# P15_4G_5G_NVME.net
KiCad netlist of a schematic drawn in Altium Designer
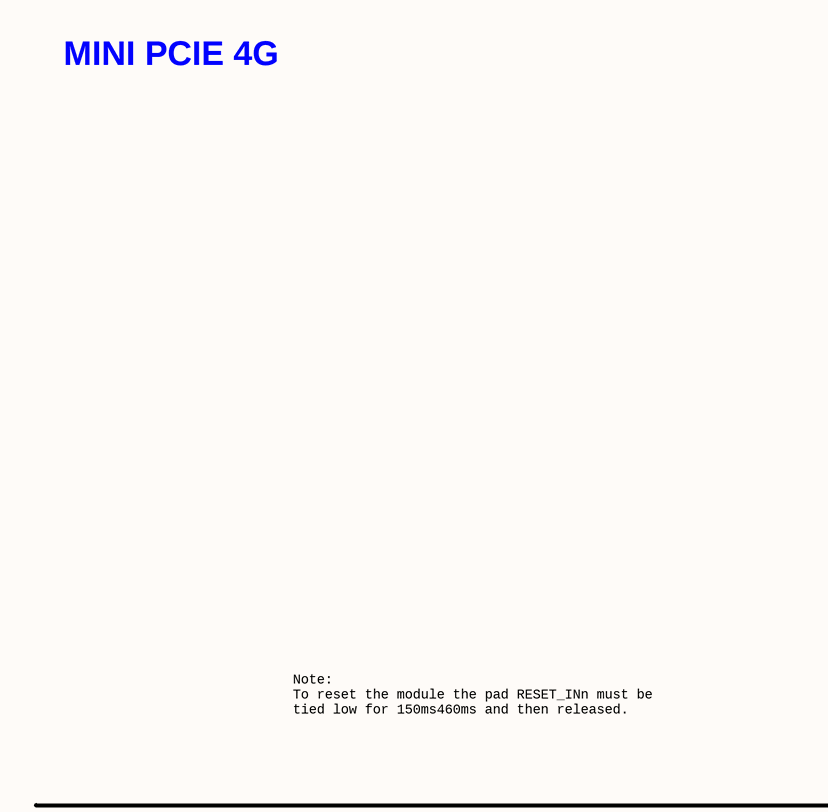
[diagram p0: P15_4G_5G_NVME.SchDoc, top left]
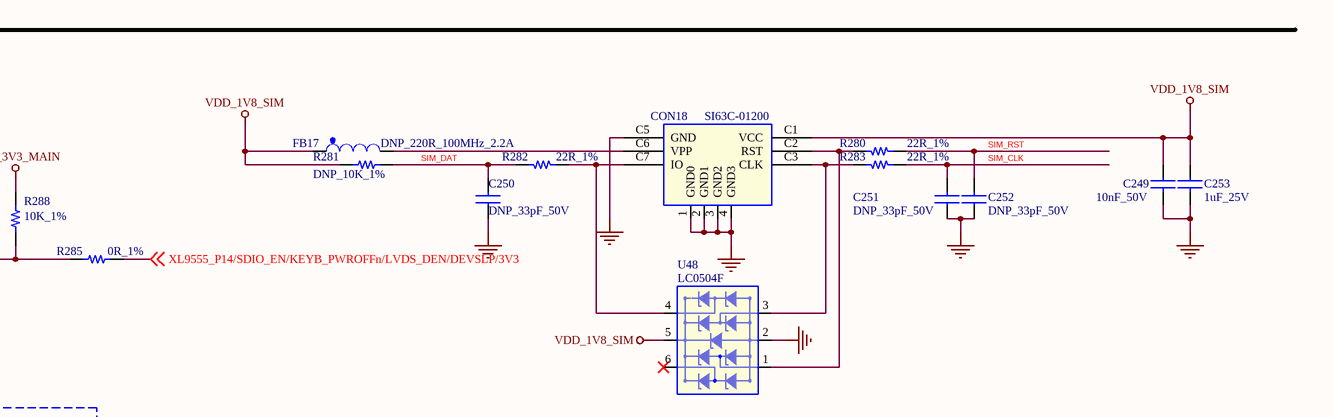
[diagram p1: P15_4G_5G_NVME.SchDoc, top right]
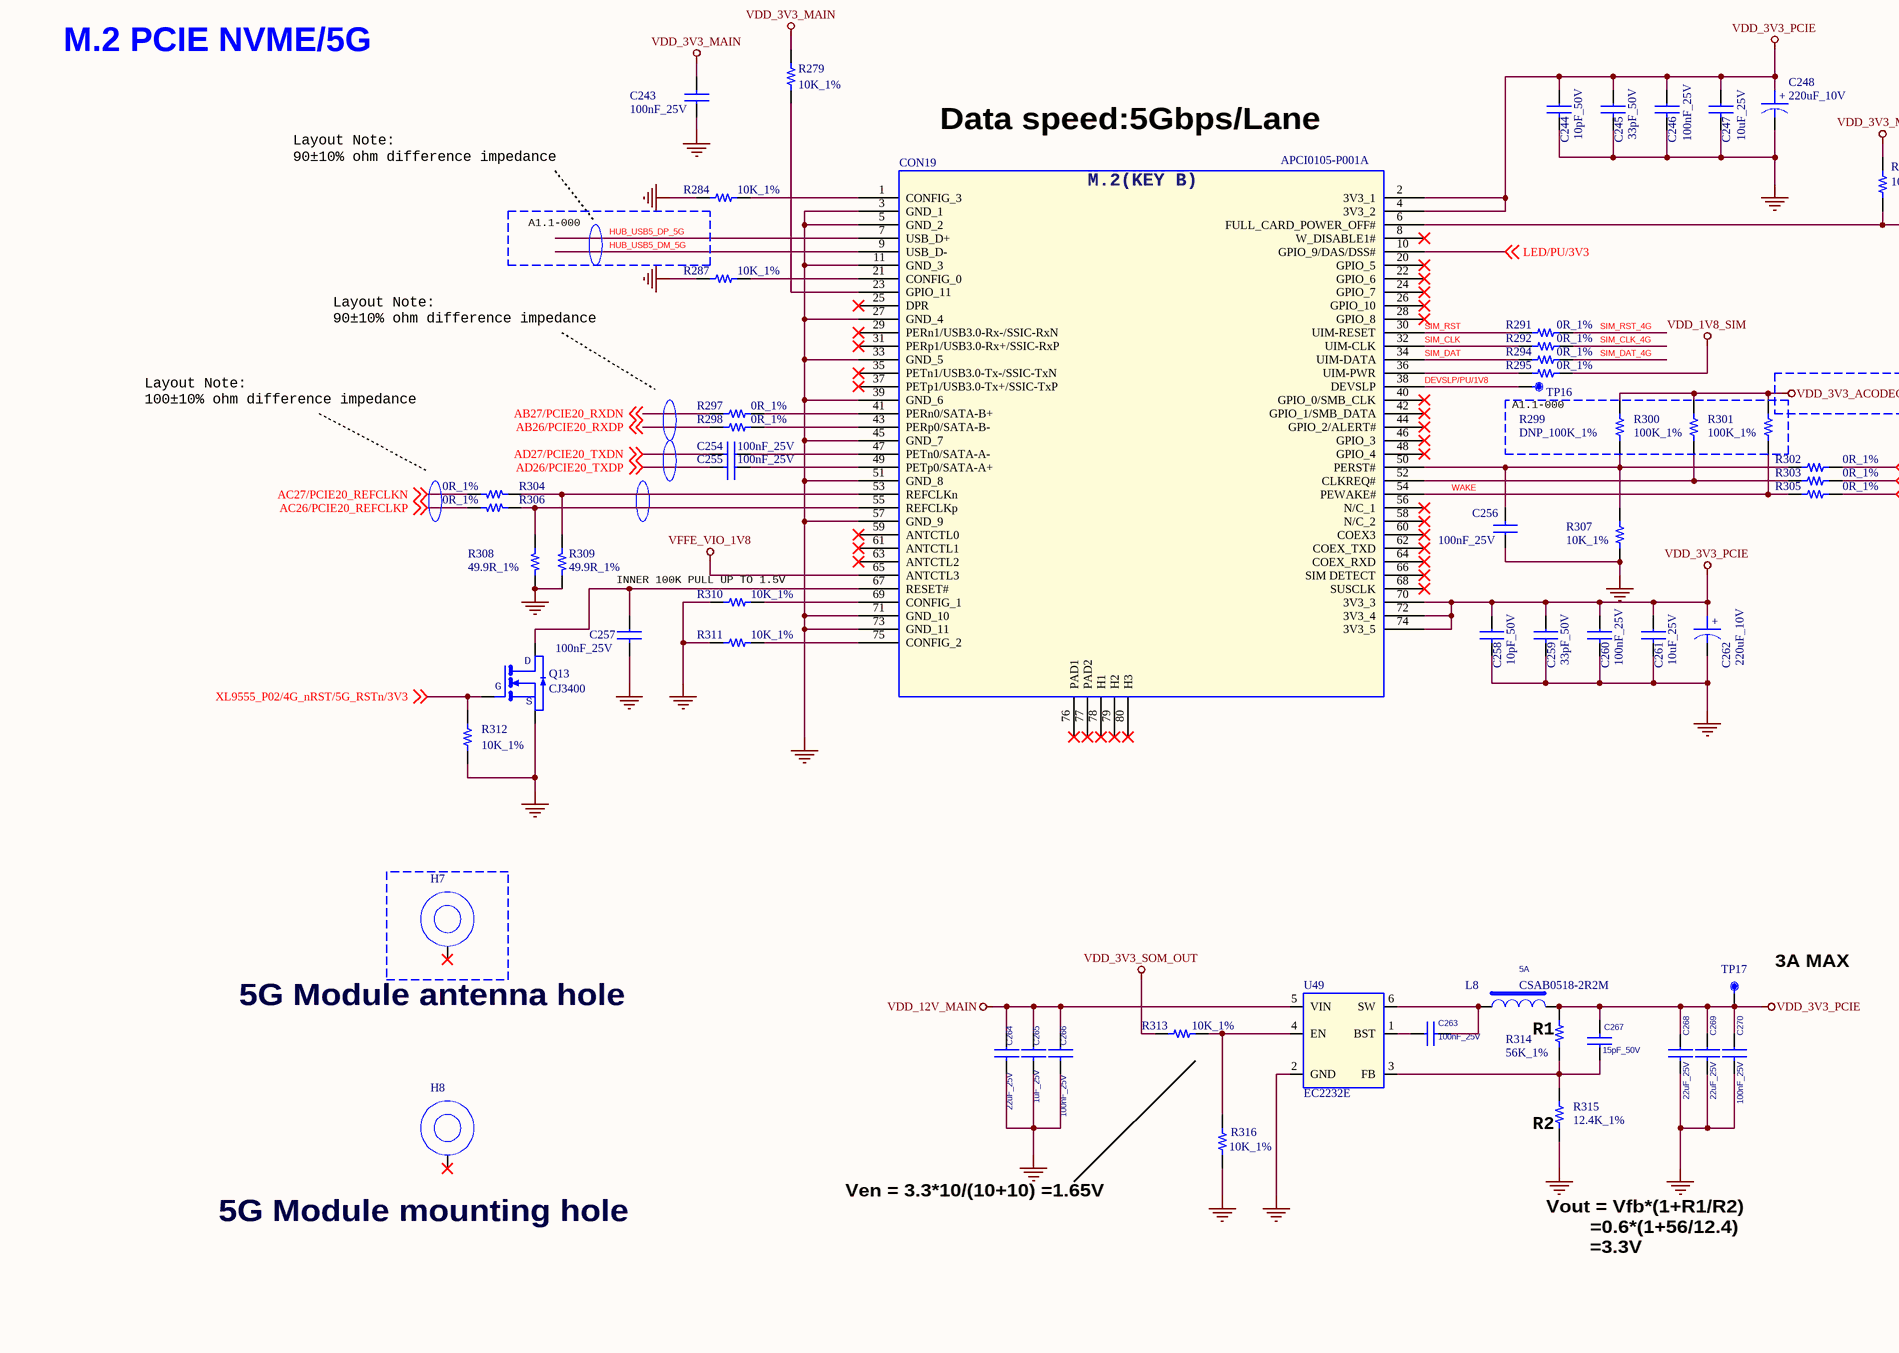
[diagram p2: P15_4G_5G_NVME.SchDoc, bottom left]
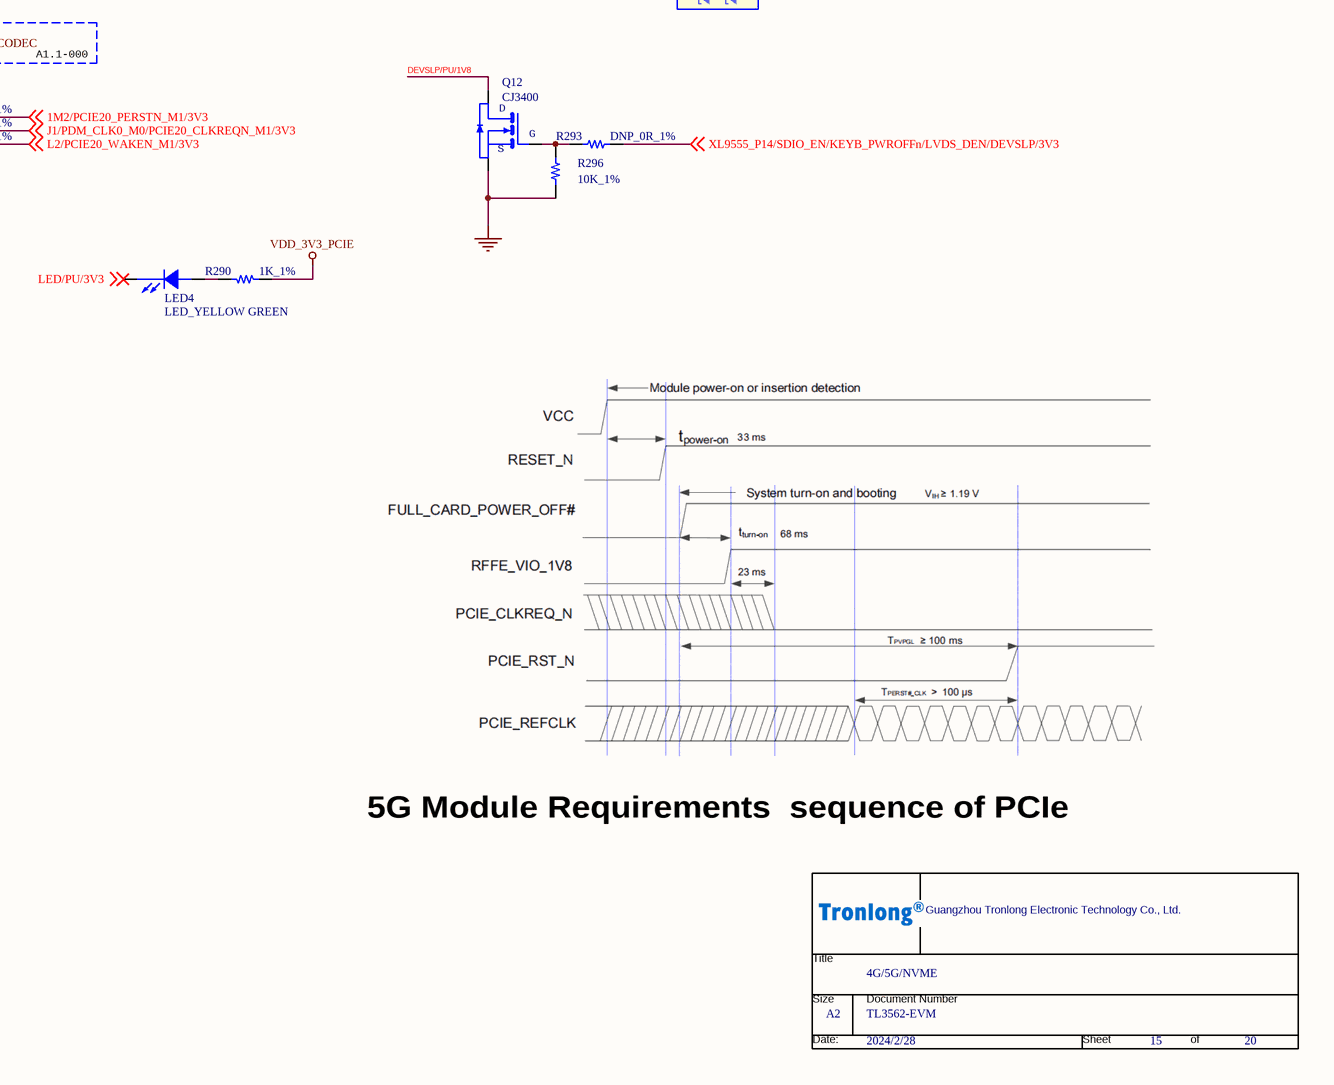
[diagram p3: P15_4G_5G_NVME.SchDoc, bottom right]

(export (version "E")
  (design (tool "Eeschema 10.0.6"))
  (components
    (comp (ref "C243")
      (value "100nF_25V")
      (footprint "C0402")
      (description "贴片陶瓷电容,100nF,10%,25V,X5R")
      (libsource (lib "*") (part "CAP NP_Dup3"))
    )
    (comp (ref "C244")
      (value "10pF_50V")
      (footprint "C0603")
      (description "贴片陶瓷电容,10pF,5%,50V,COG")
      (libsource (lib "*") (part "CAP NP_Dup3"))
    )
    (comp (ref "C245")
      (value "33pF_50V")
      (footprint "C0603")
      (description "贴片陶瓷电容,33pF,5%,50V,COG")
      (libsource (lib "*") (part "CAP NP_Dup3"))
    )
    (comp (ref "C246")
      (value "100nF_25V")
      (footprint "C0402")
      (description "贴片陶瓷电容,100nF,10%,25V,X5R")
      (libsource (lib "*") (part "CAP NP_Dup3"))
    )
    (comp (ref "C247")
      (value "10uF_25V")
      (footprint "C0603")
      (description "贴片陶瓷电容,10uF,10%,10V,X5R")
      (libsource (lib "*") (part "CAP NP_Dup3"))
    )
    (comp (ref "C248")
      (value "220uF_10V")
      (footprint "CAP_CASE_D")
      (description "D型钽电容,220uF,10%,10V")
      (fields
        (field (name "MANUFACTURER PARTNUMBER") "CA45-D010K227T")
        (field (name "MANUFACTURER") "湖南湘怡中元科技有限公司（XIANGYEE）")
      )
      (libsource (lib "*") (part "CAP POL_Dup1"))
    )
    (comp (ref "C249")
      (value "10nF_50V")
      (footprint "C0402")
      (description "贴片陶瓷电容,10nF,10%,50V,X7R")
      (libsource (lib "*") (part "CAP NP_Dup3"))
    )
    (comp (ref "C250")
      (value "DNP_33pF_50V")
      (footprint "C0603")
      (description "贴片陶瓷电容,33pF,5%,50V,COG")
      (libsource (lib "*") (part "CAP NP_Dup3"))
    )
    (comp (ref "C251")
      (value "DNP_33pF_50V")
      (footprint "C0603")
      (description "贴片陶瓷电容,33pF,5%,50V,COG")
      (libsource (lib "*") (part "CAP NP_Dup3"))
    )
    (comp (ref "C252")
      (value "DNP_33pF_50V")
      (footprint "C0603")
      (description "贴片陶瓷电容,33pF,5%,50V,COG")
      (libsource (lib "*") (part "CAP NP_Dup3"))
    )
    (comp (ref "C253")
      (value "1uF_25V")
      (footprint "C0603")
      (description "贴片陶瓷电容,1uF,10%,25V,X5R")
      (libsource (lib "*") (part "CAP NP_Dup3"))
    )
    (comp (ref "C254")
      (value "100nF_25V")
      (footprint "C0402")
      (description "贴片陶瓷电容,100nF,10%,25V,X5R")
      (libsource (lib "*") (part "CAP NP_Dup3"))
    )
    (comp (ref "C255")
      (value "100nF_25V")
      (footprint "C0402")
      (description "贴片陶瓷电容,100nF,10%,25V,X5R")
      (libsource (lib "*") (part "CAP NP_Dup3"))
    )
    (comp (ref "C256")
      (value "100nF_25V")
      (footprint "C0402")
      (description "贴片陶瓷电容,100nF,10%,25V,X5R")
      (libsource (lib "*") (part "CAP NP_Dup3"))
    )
    (comp (ref "C257")
      (value "100nF_25V")
      (footprint "C0402")
      (description "贴片陶瓷电容,100nF,10%,25V,X5R")
      (libsource (lib "*") (part "CAP NP_Dup3"))
    )
    (comp (ref "C258")
      (value "10pF_50V")
      (footprint "C0603")
      (description "贴片陶瓷电容,10pF,5%,50V,COG")
      (libsource (lib "*") (part "CAP NP_Dup3"))
    )
    (comp (ref "C259")
      (value "33pF_50V")
      (footprint "C0603")
      (description "贴片陶瓷电容,33pF,5%,50V,COG")
      (libsource (lib "*") (part "CAP NP_Dup3"))
    )
    (comp (ref "C260")
      (value "100nF_25V")
      (footprint "C0402")
      (description "贴片陶瓷电容,100nF,10%,25V,X5R")
      (libsource (lib "*") (part "CAP NP_Dup3"))
    )
    (comp (ref "C261")
      (value "10uF_25V")
      (footprint "C0603")
      (description "贴片陶瓷电容,10uF,10%,10V,X5R")
      (libsource (lib "*") (part "CAP NP_Dup3"))
    )
    (comp (ref "C262")
      (value "220uF_10V")
      (footprint "CAP_CASE_D")
      (description "D型钽电容,220uF,10%,10V")
      (fields
        (field (name "MANUFACTURER PARTNUMBER") "CA45-D010K227T")
        (field (name "MANUFACTURER") "湖南湘怡中元科技有限公司（XIANGYEE）")
      )
      (libsource (lib "*") (part "CAP POL_Dup1"))
    )
    (comp (ref "C263")
      (value "100nF_25V")
      (footprint "C0402")
      (description "贴片陶瓷电容,100nF,10%,25V,X5R")
      (libsource (lib "*") (part "CAP NP_Dup3"))
    )
    (comp (ref "C264")
      (value "22uF_25V")
      (footprint "C0805")
      (description "贴片陶瓷电容,22uF,20%,25V,X5R")
      (libsource (lib "*") (part "CAP NP_Dup3"))
    )
    (comp (ref "C265")
      (value "1uF_25V")
      (footprint "C0603")
      (description "贴片陶瓷电容,1uF,10%,25V,X5R")
      (libsource (lib "*") (part "CAP NP_Dup3"))
    )
    (comp (ref "C266")
      (value "100nF_25V")
      (footprint "C0402")
      (description "贴片陶瓷电容,100nF,10%,25V,X5R")
      (libsource (lib "*") (part "CAP NP_Dup3"))
    )
    (comp (ref "C267")
      (value "15pF_50V")
      (footprint "C0402")
      (description "贴片陶瓷电容,15pF,5%,50V,COG")
      (libsource (lib "*") (part "CAP NP_Dup3"))
    )
    (comp (ref "C268")
      (value "22uF_25V")
      (footprint "C0805")
      (description "贴片陶瓷电容,22uF,20%,25V,X5R")
      (libsource (lib "*") (part "CAP NP_Dup3"))
    )
    (comp (ref "C269")
      (value "22uF_25V")
      (footprint "C0805")
      (description "贴片陶瓷电容,22uF,20%,25V,X5R")
      (libsource (lib "*") (part "CAP NP_Dup3"))
    )
    (comp (ref "C270")
      (value "100nF_25V")
      (footprint "C0402")
      (description "贴片陶瓷电容,100nF,10%,25V,X5R")
      (libsource (lib "*") (part "CAP NP_Dup3"))
    )
    (comp (ref "CON18")
      (value "SI63C-01200")
      (footprint "micro-sim")
      (description "Micro SIM卡座,6P,自弹")
      (fields (field (name "MANUFACTURER") "深圳市爱特姆科技有限公司( ATOM)"))
      (libsource (lib "*") (part "SIM_CARD_2"))
    )
    (comp (ref "CON19")
      (value "APCI0105-P001A")
      (footprint "conn-smd_apci0103-p001a")
      (description "NGFF（M.2）金手指连接器，KEY B,高4.2mm")
      (fields (field (name "MANUFACTURER") "深圳市连欣科技有限公司"))
      (libsource (lib "*") (part "CON_M_1"))
    )
    (comp (ref "FB17")
      (value "DNP_220R_100MHz_2.2A")
      (footprint "L0603")
      (description "磁珠,50mΩ,2.2A,220R@100MHz")
      (fields
        (field (name "MANUFACTURER") "深圳顺络电子股份有限公司（Sunlord）")
        (field (name "MANUFACTURER PARTNUMBER") "UPZ1608U221-2R2TF")
      )
      (libsource (lib "*") (part "FB_0"))
    )
    (comp (ref "H7") (value "HOLE") (footprint "NHOLE_C4_BT") (libsource (lib "*") (part "HOLE")))
    (comp (ref "H8") (value "HOLE") (footprint "5G_HOLE_3D5") (libsource (lib "*") (part "HOLE")))
    (comp (ref "L8")
      (value "CSAB0518-2R2M")
      (footprint "SMD_CSAB0518")
      (description "贴片功率电感,2.2uH,0.035Ω,Isat=6.5A,Irms=5A")
      (fields (field (name "MANUFACTURER") "深圳市科达嘉电子有限公司（CODACA）") (field (name "CURRENT") "5A"))
      (libsource (lib "*") (part "INDUCTOR"))
    )
    (comp (ref "LED4")
      (value "LED_YELLOW GREEN")
      (footprint "D0603")
      (description "贴片式发光二极管,黄绿色,普亮")
      (fields
        (field (name "MANUFACTURER") "东莞市亿晶源光电科技有限公司（ekinglux）")
        (field (name "MANUFACTURER PARTNUMBER") "E6C0603YGAC1UDA")
      )
      (libsource (lib "*") (part "LED_0"))
    )
    (comp (ref "Q12")
      (value "CJ3400")
      (footprint "SOT23-3_DBZ3")
      (description "MOSFET,N沟道,VDSS=30V,VGSS=±12V,ID=5.8A,PD=0.35W,VGS(th)=1.4V")
      (fields (field (name "MANUFACTURER") "江苏长晶科技股份有限公司（JSCJ）"))
      (libsource (lib "*") (part "MMBT3904/SOT_1"))
    )
    (comp (ref "Q13")
      (value "CJ3400")
      (footprint "SOT23-3_DBZ3")
      (description "MOSFET,N沟道,VDSS=30V,VGSS=±12V,ID=5.8A,PD=0.35W,VGS(th)=1.4V")
      (fields (field (name "MANUFACTURER") "江苏长晶科技股份有限公司（JSCJ）"))
      (libsource (lib "*") (part "MOSFET N SOT"))
    )
    (comp (ref "R279")
      (value "10K_1%")
      (footprint "R0402")
      (description "贴片电阻,10K,±1%,1/16W")
      (libsource (lib "*") (part "Resistor_Dup3"))
    )
    (comp (ref "R280")
      (value "22R_1%")
      (footprint "R0402")
      (description "贴片电阻,22R,±1%,1/16W")
      (libsource (lib "*") (part "Resistor_Dup3"))
    )
    (comp (ref "R281")
      (value "DNP_10K_1%")
      (footprint "R0402")
      (description "贴片电阻,10K,±1%,1/16W")
      (libsource (lib "*") (part "Resistor_Dup3"))
    )
    (comp (ref "R282")
      (value "22R_1%")
      (footprint "R0402")
      (description "贴片电阻,22R,±1%,1/16W")
      (libsource (lib "*") (part "Resistor_Dup3"))
    )
    (comp (ref "R283")
      (value "22R_1%")
      (footprint "R0402")
      (description "贴片电阻,22R,±1%,1/16W")
      (libsource (lib "*") (part "Resistor_Dup3"))
    )
    (comp (ref "R284")
      (value "10K_1%")
      (footprint "R0402")
      (description "贴片电阻,10K,±1%,1/16W")
      (libsource (lib "*") (part "Resistor_Dup3"))
    )
    (comp (ref "R285")
      (value "0R_1%")
      (footprint "R0402")
      (description "贴片电阻,0R,±1%,1/16W")
      (libsource (lib "*") (part "Resistor_Dup3"))
    )
    (comp (ref "R287")
      (value "10K_1%")
      (footprint "R0402")
      (description "贴片电阻,10K,±1%,1/16W")
      (libsource (lib "*") (part "Resistor_Dup3"))
    )
    (comp (ref "R288")
      (value "10K_1%")
      (footprint "R0402")
      (description "贴片电阻,10K,±1%,1/16W")
      (libsource (lib "*") (part "Resistor_Dup3"))
    )
    (comp (ref "R290")
      (value "1K_1%")
      (footprint "R0402")
      (description "贴片电阻,1K,±1%,1/16W")
      (libsource (lib "*") (part "R 1%"))
    )
    (comp (ref "R291")
      (value "0R_1%")
      (footprint "R0402")
      (description "贴片电阻,0R,±1%,1/16W")
      (libsource (lib "*") (part "Resistor_Dup3"))
    )
    (comp (ref "R292")
      (value "0R_1%")
      (footprint "R0402")
      (description "贴片电阻,0R,±1%,1/16W")
      (libsource (lib "*") (part "Resistor_Dup3"))
    )
    (comp (ref "R293")
      (value "DNP_0R_1%")
      (footprint "R0402")
      (description "贴片电阻,0R,±1%,1/16W")
      (libsource (lib "*") (part "Resistor_Dup3"))
    )
    (comp (ref "R294")
      (value "0R_1%")
      (footprint "R0402")
      (description "贴片电阻,0R,±1%,1/16W")
      (libsource (lib "*") (part "Resistor_Dup3"))
    )
    (comp (ref "R295")
      (value "0R_1%")
      (footprint "R0603")
      (description "贴片电阻,0R,±1%,1/10W")
      (libsource (lib "*") (part "Resistor_Dup3"))
    )
    (comp (ref "R296")
      (value "10K_1%")
      (footprint "R0402")
      (description "贴片电阻,10K,±1%,1/16W")
      (libsource (lib "*") (part "Resistor_Dup3"))
    )
    (comp (ref "R297")
      (value "0R_1%")
      (footprint "R0402")
      (description "贴片电阻,0R,±1%,1/16W")
      (libsource (lib "*") (part "Resistor_Dup3"))
    )
    (comp (ref "R298")
      (value "0R_1%")
      (footprint "R0402")
      (description "贴片电阻,0R,±1%,1/16W")
      (libsource (lib "*") (part "Resistor_Dup3"))
    )
    (comp (ref "R299")
      (value "DNP_100K_1%")
      (footprint "R0402")
      (description "贴片电阻,100K,±1%,1/16W")
      (libsource (lib "*") (part "Resistor_Dup3"))
    )
    (comp (ref "R300")
      (value "100K_1%")
      (footprint "R0402")
      (description "贴片电阻,100K,±1%,1/16W")
      (libsource (lib "*") (part "Resistor_Dup3"))
    )
    (comp (ref "R301")
      (value "100K_1%")
      (footprint "R0402")
      (description "贴片电阻,100K,±1%,1/16W")
      (libsource (lib "*") (part "Resistor_Dup3"))
    )
    (comp (ref "R302")
      (value "0R_1%")
      (footprint "R0402")
      (description "贴片电阻,0R,±1%,1/16W")
      (libsource (lib "*") (part "Resistor_Dup3"))
    )
    (comp (ref "R303")
      (value "0R_1%")
      (footprint "R0402")
      (description "贴片电阻,0R,±1%,1/16W")
      (libsource (lib "*") (part "Resistor_Dup3"))
    )
    (comp (ref "R304")
      (value "0R_1%")
      (footprint "R0402")
      (description "贴片电阻,0R,±1%,1/16W")
      (libsource (lib "*") (part "Resistor_Dup3"))
    )
    (comp (ref "R305")
      (value "0R_1%")
      (footprint "R0402")
      (description "贴片电阻,0R,±1%,1/16W")
      (libsource (lib "*") (part "Resistor_Dup3"))
    )
    (comp (ref "R306")
      (value "0R_1%")
      (footprint "R0402")
      (description "贴片电阻,0R,±1%,1/16W")
      (libsource (lib "*") (part "Resistor_Dup3"))
    )
    (comp (ref "R307")
      (value "10K_1%")
      (footprint "R0402")
      (description "贴片电阻,10K,±1%,1/16W")
      (libsource (lib "*") (part "Resistor_Dup3"))
    )
    (comp (ref "R308")
      (value "49.9R_1%")
      (footprint "R0603")
      (description "贴片电阻,49.9R,±1%,1/10W")
      (libsource (lib "*") (part "Resistor_Dup3"))
    )
    (comp (ref "R309")
      (value "49.9R_1%")
      (footprint "R0603")
      (description "贴片电阻,49.9R,±1%,1/10W")
      (libsource (lib "*") (part "Resistor_Dup3"))
    )
    (comp (ref "R310")
      (value "10K_1%")
      (footprint "R0402")
      (description "贴片电阻,10K,±1%,1/16W")
      (libsource (lib "*") (part "Resistor_Dup3"))
    )
    (comp (ref "R311")
      (value "10K_1%")
      (footprint "R0402")
      (description "贴片电阻,10K,±1%,1/16W")
      (libsource (lib "*") (part "Resistor_Dup3"))
    )
    (comp (ref "R312")
      (value "10K_1%")
      (footprint "R0402")
      (description "贴片电阻,10K,±1%,1/16W")
      (libsource (lib "*") (part "Resistor_Dup3"))
    )
    (comp (ref "R313")
      (value "10K_1%")
      (footprint "R0402")
      (description "贴片电阻,10K,±1%,1/16W")
      (libsource (lib "*") (part "Resistor_Dup3"))
    )
    (comp (ref "R314")
      (value "56K_1%")
      (footprint "R0402")
      (description "贴片电阻,56K,±1%,1/16W")
      (libsource (lib "*") (part "Resistor_Dup3"))
    )
    (comp (ref "R315")
      (value "12.4K_1%")
      (footprint "R0402")
      (description "贴片电阻,12.4K,±1%,1/16W")
      (libsource (lib "*") (part "Resistor_Dup3"))
    )
    (comp (ref "R316")
      (value "10K_1%")
      (footprint "R0402")
      (description "贴片电阻,10K,±1%,1/16W")
      (libsource (lib "*") (part "Resistor_Dup3"))
    )
    (comp (ref "TP16") (value "SMT TP") (footprint "TP-S40") (libsource (lib "*") (part "TP-S40")))
    (comp (ref "TP17") (value "SMT TP") (footprint "TP-S40") (libsource (lib "*") (part "TP-S40")))
    (comp (ref "U48")
      (value "LC0504F")
      (footprint "SOT363")
      (description "ESD二极管,VRWM=5V,VBR=6V,四组,单向,8KV,15KV")
      (fields
        (field (name "MANUFACTURER") "上海雷卯电子科技有限公司（Leiditech）")
        (field (name "MANUFACTURER PART NUMBER") "PRTR5V0U4Y")
      )
      (libsource (lib "*") (part "PRTR5V0U4Y_0"))
    )
    (comp (ref "U49")
      (value "EC2232E")
      (footprint "SOT-23-6L")
      (description "DC/DC,Buck,Vin:4.5V~17V,Vout:0.6V~6V,3A,1路")
      (fields (field (name "MANUFACTURER") "上海芯强微电子股份有限公司（Ecranic）"))
      (libsource (lib "*") (part "WD1304E30"))
    )
  )
  (nets
    (net (code "1") (name "/DEVSLP{slash}PU{slash}1V8") (class "Default")
      (node (ref "CON19") (pin "38") (pinfunction "DEVSLP_38") (pintype "passive"))
      (node (ref "Q12") (pin "3") (pinfunction "C_3") (pintype "passive"))
      (node (ref "TP16") (pin "1") (pinfunction "1_1") (pintype "passive"))
    )
    (net (code "2") (name "/HUB_USB5_DM_5G") (class "Default")
      (node (ref "CON19") (pin "9") (pinfunction "USB_D-_9") (pintype "passive"))
    )
    (net (code "3") (name "/HUB_USB5_DP_5G") (class "Default")
      (node (ref "CON19") (pin "7") (pinfunction "USB_D+_7") (pintype "passive"))
    )
    (net (code "4") (name "/SIM_CLK") (class "Default")
      (node (ref "C251") (pin "2") (pinfunction "2_2") (pintype "passive"))
      (node (ref "CON19") (pin "32") (pinfunction "UIM-CLK_32") (pintype "passive"))
      (node (ref "R283") (pin "2") (pinfunction "2_2") (pintype "passive"))
      (node (ref "R292") (pin "2") (pinfunction "2_2") (pintype "passive"))
    )
    (net (code "5") (name "/SIM_CLK_4G") (class "Default")
      (node (ref "R292") (pin "1") (pinfunction "1_1") (pintype "passive"))
    )
    (net (code "6") (name "/SIM_DAT") (class "Default")
      (node (ref "C250") (pin "2") (pinfunction "2_2") (pintype "passive"))
      (node (ref "CON19") (pin "34") (pinfunction "UIM-DATA_34") (pintype "passive"))
      (node (ref "R281") (pin "2") (pinfunction "2_2") (pintype "passive"))
      (node (ref "R282") (pin "1") (pinfunction "1_1") (pintype "passive"))
      (node (ref "R294") (pin "2") (pinfunction "2_2") (pintype "passive"))
    )
    (net (code "7") (name "/SIM_DAT_4G") (class "Default")
      (node (ref "R294") (pin "1") (pinfunction "1_1") (pintype "passive"))
    )
    (net (code "8") (name "/SIM_RST") (class "Default")
      (node (ref "C252") (pin "2") (pinfunction "2_2") (pintype "passive"))
      (node (ref "CON19") (pin "30") (pinfunction "UIM-RESET_30") (pintype "passive"))
      (node (ref "R280") (pin "2") (pinfunction "2_2") (pintype "passive"))
      (node (ref "R291") (pin "2") (pinfunction "2_2") (pintype "passive"))
    )
    (net (code "9") (name "/SIM_RST_4G") (class "Default")
      (node (ref "R291") (pin "1") (pinfunction "1_1") (pintype "passive"))
    )
    (net (code "10") (name "/WAKE") (class "Default")
      (node (ref "CON19") (pin "54") (pinfunction "PEWAKE#_54") (pintype "passive"))
      (node (ref "R301") (pin "2") (pinfunction "2_2") (pintype "passive"))
      (node (ref "R305") (pin "2") (pinfunction "2_2") (pintype "passive"))
    )
    (net (code "11") (name "1M2{slash}PCIE20_PERSTN_M1{slash}3V3") (class "Default")
      (node (ref "R302") (pin "1") (pinfunction "1_1") (pintype "passive"))
    )
    (net (code "12") (name "AB26{slash}PCIE20_RXDP") (class "Default")
      (node (ref "R298") (pin "1") (pinfunction "1_1") (pintype "passive"))
    )
    (net (code "13") (name "AB27{slash}PCIE20_RXDN") (class "Default")
      (node (ref "R297") (pin "1") (pinfunction "1_1") (pintype "passive"))
    )
    (net (code "14") (name "AC26{slash}PCIE20_REFCLKP") (class "Default")
      (node (ref "R306") (pin "2") (pinfunction "2_2") (pintype "passive"))
    )
    (net (code "15") (name "AC27{slash}PCIE20_REFCLKN") (class "Default")
      (node (ref "R304") (pin "2") (pinfunction "2_2") (pintype "passive"))
    )
    (net (code "16") (name "AD26{slash}PCIE20_TXDP") (class "Default")
      (node (ref "C255") (pin "2") (pinfunction "2_2") (pintype "passive"))
    )
    (net (code "17") (name "AD27{slash}PCIE20_TXDN") (class "Default")
      (node (ref "C254") (pin "2") (pinfunction "2_2") (pintype "passive"))
    )
    (net (code "18") (name "GND") (class "Default")
      (node (ref "C243") (pin "1") (pinfunction "1_1") (pintype "passive"))
      (node (ref "C244") (pin "2") (pinfunction "2_2") (pintype "passive"))
      (node (ref "C245") (pin "2") (pinfunction "2_2") (pintype "passive"))
      (node (ref "C246") (pin "2") (pinfunction "2_2") (pintype "passive"))
      (node (ref "C247") (pin "2") (pinfunction "2_2") (pintype "passive"))
      (node (ref "C248") (pin "2") (pinfunction "2_2") (pintype "passive"))
      (node (ref "C249") (pin "2") (pinfunction "2_2") (pintype "passive"))
      (node (ref "C250") (pin "1") (pinfunction "1_1") (pintype "passive"))
      (node (ref "C251") (pin "1") (pinfunction "1_1") (pintype "passive"))
      (node (ref "C252") (pin "1") (pinfunction "1_1") (pintype "passive"))
      (node (ref "C253") (pin "2") (pinfunction "2_2") (pintype "passive"))
      (node (ref "C256") (pin "1") (pinfunction "1_1") (pintype "passive"))
      (node (ref "C257") (pin "2") (pinfunction "2_2") (pintype "passive"))
      (node (ref "C258") (pin "2") (pinfunction "2_2") (pintype "passive"))
      (node (ref "C259") (pin "2") (pinfunction "2_2") (pintype "passive"))
      (node (ref "C260") (pin "2") (pinfunction "2_2") (pintype "passive"))
      (node (ref "C261") (pin "2") (pinfunction "2_2") (pintype "passive"))
      (node (ref "C262") (pin "2") (pinfunction "2_2") (pintype "passive"))
      (node (ref "C264") (pin "2") (pinfunction "2_2") (pintype "passive"))
      (node (ref "C265") (pin "2") (pinfunction "2_2") (pintype "passive"))
      (node (ref "C266") (pin "2") (pinfunction "2_2") (pintype "passive"))
      (node (ref "C268") (pin "2") (pinfunction "2_2") (pintype "passive"))
      (node (ref "C269") (pin "2") (pinfunction "2_2") (pintype "passive"))
      (node (ref "C270") (pin "2") (pinfunction "2_2") (pintype "passive"))
      (node (ref "CON18") (pin "1") (pinfunction "GND0_1") (pintype "passive"))
      (node (ref "CON18") (pin "2") (pinfunction "GND1_2") (pintype "passive"))
      (node (ref "CON18") (pin "3") (pinfunction "GND2_3") (pintype "passive"))
      (node (ref "CON18") (pin "4") (pinfunction "GND3_4") (pintype "passive"))
      (node (ref "CON18") (pin "C5") (pinfunction "GND_C5") (pintype "passive"))
      (node (ref "CON19") (pin "11") (pinfunction "GND_3_11") (pintype "passive"))
      (node (ref "CON19") (pin "27") (pinfunction "GND_4_27") (pintype "passive"))
      (node (ref "CON19") (pin "3") (pinfunction "GND_1_3") (pintype "passive"))
      (node (ref "CON19") (pin "33") (pinfunction "GND_5_33") (pintype "passive"))
      (node (ref "CON19") (pin "39") (pinfunction "GND_6_39") (pintype "passive"))
      (node (ref "CON19") (pin "45") (pinfunction "GND_7_45") (pintype "passive"))
      (node (ref "CON19") (pin "5") (pinfunction "GND_2_5") (pintype "passive"))
      (node (ref "CON19") (pin "51") (pinfunction "GND_8_51") (pintype "passive"))
      (node (ref "CON19") (pin "57") (pinfunction "GND_9_57") (pintype "passive"))
      (node (ref "CON19") (pin "71") (pinfunction "GND_10_71") (pintype "passive"))
      (node (ref "CON19") (pin "73") (pinfunction "GND_11_73") (pintype "passive"))
      (node (ref "Q12") (pin "2") (pinfunction "E_2") (pintype "passive"))
      (node (ref "Q13") (pin "2") (pinfunction "E_2") (pintype "passive"))
      (node (ref "R284") (pin "2") (pinfunction "2_2") (pintype "passive"))
      (node (ref "R287") (pin "2") (pinfunction "2_2") (pintype "passive"))
      (node (ref "R296") (pin "2") (pinfunction "2_2") (pintype "passive"))
      (node (ref "R307") (pin "2") (pinfunction "2_2") (pintype "passive"))
      (node (ref "R308") (pin "1") (pinfunction "1_1") (pintype "passive"))
      (node (ref "R309") (pin "1") (pinfunction "1_1") (pintype "passive"))
      (node (ref "R310") (pin "2") (pinfunction "2_2") (pintype "passive"))
      (node (ref "R311") (pin "2") (pinfunction "2_2") (pintype "passive"))
      (node (ref "R312") (pin "2") (pinfunction "2_2") (pintype "passive"))
      (node (ref "R315") (pin "1") (pinfunction "1_1") (pintype "passive"))
      (node (ref "R316") (pin "1") (pinfunction "1_1") (pintype "passive"))
      (node (ref "U48") (pin "2") (pinfunction "2_2") (pintype "passive"))
      (node (ref "U49") (pin "2") (pinfunction "GND_2") (pintype "power_in"))
    )
    (net (code "19") (name "J1{slash}PDM_CLK0_M0{slash}PCIE20_CLKREQN_M1{slash}3V3") (class "Default")
      (node (ref "R303") (pin "1") (pinfunction "1_1") (pintype "passive"))
    )
    (net (code "20") (name "L2{slash}PCIE20_WAKEN_M1{slash}3V3") (class "Default")
      (node (ref "R305") (pin "1") (pinfunction "1_1") (pintype "passive"))
    )
    (net (code "21") (name "LED{slash}PU{slash}3V3") (class "Default")
      (node (ref "CON19") (pin "10") (pinfunction "GPIO_9/DAS/DSS#_10") (pintype "passive"))
      (node (ref "LED4") (pin "2") (pinfunction "ANODE_2") (pintype "passive"))
    )
    (net (code "22") (name "Net-(CON18-CLK)") (class "Default")
      (node (ref "CON18") (pin "C3") (pinfunction "CLK_C3") (pintype "passive"))
      (node (ref "R283") (pin "1") (pinfunction "1_1") (pintype "passive"))
      (node (ref "U48") (pin "3") (pinfunction "3_3") (pintype "passive"))
    )
    (net (code "23") (name "Net-(CON18-IO)") (class "Default")
      (node (ref "CON18") (pin "C7") (pinfunction "IO_C7") (pintype "passive"))
      (node (ref "R282") (pin "2") (pinfunction "2_2") (pintype "passive"))
      (node (ref "U48") (pin "4") (pinfunction "4_4") (pintype "passive"))
    )
    (net (code "24") (name "Net-(CON18-RST)") (class "Default")
      (node (ref "CON18") (pin "C2") (pinfunction "RST_C2") (pintype "passive"))
      (node (ref "R280") (pin "1") (pinfunction "1_1") (pintype "passive"))
      (node (ref "U48") (pin "1") (pinfunction "1_1") (pintype "passive"))
    )
    (net (code "25") (name "Net-(CON18-VPP)") (class "Default")
      (node (ref "CON18") (pin "C6") (pinfunction "VPP_C6") (pintype "passive"))
      (node (ref "FB17") (pin "2") (pinfunction "2_2") (pintype "passive"))
    )
    (net (code "26") (name "Net-(CON19-CLKREQ#)") (class "Default")
      (node (ref "CON19") (pin "52") (pinfunction "CLKREQ#_52") (pintype "passive"))
      (node (ref "R300") (pin "2") (pinfunction "2_2") (pintype "passive"))
      (node (ref "R303") (pin "2") (pinfunction "2_2") (pintype "passive"))
    )
    (net (code "27") (name "Net-(CON19-CONFIG_0)") (class "Default")
      (node (ref "CON19") (pin "21") (pinfunction "CONFIG_0_21") (pintype "passive"))
      (node (ref "R287") (pin "1") (pinfunction "1_1") (pintype "passive"))
    )
    (net (code "28") (name "Net-(CON19-CONFIG_1)") (class "Default")
      (node (ref "CON19") (pin "69") (pinfunction "CONFIG_1_69") (pintype "passive"))
      (node (ref "R310") (pin "1") (pinfunction "1_1") (pintype "passive"))
    )
    (net (code "29") (name "Net-(CON19-CONFIG_2)") (class "Default")
      (node (ref "CON19") (pin "75") (pinfunction "CONFIG_2_75") (pintype "passive"))
      (node (ref "R311") (pin "1") (pinfunction "1_1") (pintype "passive"))
    )
    (net (code "30") (name "Net-(CON19-CONFIG_3)") (class "Default")
      (node (ref "CON19") (pin "1") (pinfunction "CONFIG_3_1") (pintype "passive"))
      (node (ref "R284") (pin "1") (pinfunction "1_1") (pintype "passive"))
    )
    (net (code "31") (name "Net-(CON19-FULL_CARD_POWER_OFF#)") (class "Default")
      (node (ref "CON19") (pin "6") (pinfunction "FULL_CARD_POWER_OFF#_6") (pintype "passive"))
      (node (ref "R285") (pin "2") (pinfunction "2_2") (pintype "passive"))
      (node (ref "R288") (pin "2") (pinfunction "2_2") (pintype "passive"))
    )
    (net (code "32") (name "Net-(CON19-GPIO_11)") (class "Default")
      (node (ref "CON19") (pin "23") (pinfunction "GPIO_11_23") (pintype "passive"))
      (node (ref "R279") (pin "2") (pinfunction "2_2") (pintype "passive"))
    )
    (net (code "33") (name "Net-(CON19-PERST#)") (class "Default")
      (node (ref "C256") (pin "2") (pinfunction "2_2") (pintype "passive"))
      (node (ref "CON19") (pin "50") (pinfunction "PERST#_50") (pintype "passive"))
      (node (ref "R299") (pin "2") (pinfunction "2_2") (pintype "passive"))
      (node (ref "R302") (pin "2") (pinfunction "2_2") (pintype "passive"))
      (node (ref "R307") (pin "1") (pinfunction "1_1") (pintype "passive"))
    )
    (net (code "34") (name "Net-(CON19-PERn0{slash}SATA-B+)") (class "Default")
      (node (ref "CON19") (pin "41") (pinfunction "PERn0/SATA-B+_41") (pintype "passive"))
      (node (ref "R297") (pin "2") (pinfunction "2_2") (pintype "passive"))
    )
    (net (code "35") (name "Net-(CON19-PERp0{slash}SATA-B-)") (class "Default")
      (node (ref "CON19") (pin "43") (pinfunction "PERp0/SATA-B-_43") (pintype "passive"))
      (node (ref "R298") (pin "2") (pinfunction "2_2") (pintype "passive"))
    )
    (net (code "36") (name "Net-(CON19-PETn0{slash}SATA-A-)") (class "Default")
      (node (ref "C254") (pin "1") (pinfunction "1_1") (pintype "passive"))
      (node (ref "CON19") (pin "47") (pinfunction "PETn0/SATA-A-_47") (pintype "passive"))
    )
    (net (code "37") (name "Net-(CON19-PETp0{slash}SATA-A+)") (class "Default")
      (node (ref "C255") (pin "1") (pinfunction "1_1") (pintype "passive"))
      (node (ref "CON19") (pin "49") (pinfunction "PETp0/SATA-A+_49") (pintype "passive"))
    )
    (net (code "38") (name "Net-(CON19-REFCLKn)") (class "Default")
      (node (ref "CON19") (pin "53") (pinfunction "REFCLKn_53") (pintype "passive"))
      (node (ref "R304") (pin "1") (pinfunction "1_1") (pintype "passive"))
      (node (ref "R309") (pin "2") (pinfunction "2_2") (pintype "passive"))
    )
    (net (code "39") (name "Net-(CON19-REFCLKp)") (class "Default")
      (node (ref "CON19") (pin "55") (pinfunction "REFCLKp_55") (pintype "passive"))
      (node (ref "R306") (pin "1") (pinfunction "1_1") (pintype "passive"))
      (node (ref "R308") (pin "2") (pinfunction "2_2") (pintype "passive"))
    )
    (net (code "40") (name "Net-(CON19-RESET#)") (class "Default")
      (node (ref "C257") (pin "1") (pinfunction "1_1") (pintype "passive"))
      (node (ref "CON19") (pin "67") (pinfunction "RESET#_67") (pintype "passive"))
      (node (ref "Q13") (pin "3") (pinfunction "C_3") (pintype "passive"))
    )
    (net (code "41") (name "Net-(CON19-UIM-PWR)") (class "Default")
      (node (ref "CON19") (pin "36") (pinfunction "UIM-PWR_36") (pintype "passive"))
      (node (ref "R295") (pin "2") (pinfunction "2_2") (pintype "passive"))
    )
    (net (code "42") (name "Net-(LED4-CATHODE)") (class "Default")
      (node (ref "LED4") (pin "1") (pinfunction "CATHODE_1") (pintype "passive"))
      (node (ref "R290") (pin "2") (pinfunction "2_2") (pintype "passive"))
    )
    (net (code "43") (name "Net-(Q12-B)") (class "Default")
      (node (ref "Q12") (pin "1") (pinfunction "B_1") (pintype "passive"))
      (node (ref "R293") (pin "1") (pinfunction "1_1") (pintype "passive"))
      (node (ref "R296") (pin "1") (pinfunction "1_1") (pintype "passive"))
    )
    (net (code "44") (name "Net-(U49-BST)") (class "Default")
      (node (ref "C263") (pin "1") (pinfunction "1_1") (pintype "passive"))
      (node (ref "U49") (pin "1") (pinfunction "BST_1") (pintype "passive"))
    )
    (net (code "45") (name "Net-(U49-EN)") (class "Default")
      (node (ref "R313") (pin "1") (pinfunction "1_1") (pintype "passive"))
      (node (ref "R316") (pin "2") (pinfunction "2_2") (pintype "passive"))
      (node (ref "U49") (pin "4") (pinfunction "EN_4") (pintype "passive"))
    )
    (net (code "46") (name "Net-(U49-FB)") (class "Default")
      (node (ref "C267") (pin "1") (pinfunction "1_1") (pintype "passive"))
      (node (ref "R314") (pin "1") (pinfunction "1_1") (pintype "passive"))
      (node (ref "R315") (pin "2") (pinfunction "2_2") (pintype "passive"))
      (node (ref "U49") (pin "3") (pinfunction "FB_3") (pintype "passive"))
    )
    (net (code "47") (name "Net-(U49-SW)") (class "Default")
      (node (ref "C263") (pin "2") (pinfunction "2_2") (pintype "passive"))
      (node (ref "L8") (pin "1") (pinfunction "1_1") (pintype "passive"))
      (node (ref "U49") (pin "6") (pinfunction "SW_6") (pintype "passive"))
    )
    (net (code "48") (name "VDD_1V8_SIM") (class "Default")
      (node (ref "C249") (pin "1") (pinfunction "1_1") (pintype "passive"))
      (node (ref "C253") (pin "1") (pinfunction "1_1") (pintype "passive"))
      (node (ref "CON18") (pin "C1") (pinfunction "VCC_C1") (pintype "passive"))
      (node (ref "FB17") (pin "1") (pinfunction "1_1") (pintype "passive"))
      (node (ref "R281") (pin "1") (pinfunction "1_1") (pintype "passive"))
      (node (ref "R295") (pin "1") (pinfunction "1_1") (pintype "passive"))
      (node (ref "U48") (pin "5") (pinfunction "5_5") (pintype "passive"))
    )
    (net (code "49") (name "VDD_3V3_ACODEC") (class "Default")
      (node (ref "R299") (pin "1") (pinfunction "1_1") (pintype "passive"))
      (node (ref "R300") (pin "1") (pinfunction "1_1") (pintype "passive"))
      (node (ref "R301") (pin "1") (pinfunction "1_1") (pintype "passive"))
    )
    (net (code "50") (name "VDD_3V3_MAIN") (class "Default")
      (node (ref "C243") (pin "2") (pinfunction "2_2") (pintype "passive"))
      (node (ref "R279") (pin "1") (pinfunction "1_1") (pintype "passive"))
      (node (ref "R288") (pin "1") (pinfunction "1_1") (pintype "passive"))
    )
    (net (code "51") (name "VDD_3V3_PCIE") (class "Default")
      (node (ref "C244") (pin "1") (pinfunction "1_1") (pintype "passive"))
      (node (ref "C245") (pin "1") (pinfunction "1_1") (pintype "passive"))
      (node (ref "C246") (pin "1") (pinfunction "1_1") (pintype "passive"))
      (node (ref "C247") (pin "1") (pinfunction "1_1") (pintype "passive"))
      (node (ref "C248") (pin "1") (pinfunction "1_1") (pintype "passive"))
      (node (ref "C258") (pin "1") (pinfunction "1_1") (pintype "passive"))
      (node (ref "C259") (pin "1") (pinfunction "1_1") (pintype "passive"))
      (node (ref "C260") (pin "1") (pinfunction "1_1") (pintype "passive"))
      (node (ref "C261") (pin "1") (pinfunction "1_1") (pintype "passive"))
      (node (ref "C262") (pin "1") (pinfunction "1_1") (pintype "passive"))
      (node (ref "C267") (pin "2") (pinfunction "2_2") (pintype "passive"))
      (node (ref "C268") (pin "1") (pinfunction "1_1") (pintype "passive"))
      (node (ref "C269") (pin "1") (pinfunction "1_1") (pintype "passive"))
      (node (ref "C270") (pin "1") (pinfunction "1_1") (pintype "passive"))
      (node (ref "CON19") (pin "2") (pinfunction "3V3_1_2") (pintype "passive"))
      (node (ref "CON19") (pin "4") (pinfunction "3V3_2_4") (pintype "passive"))
      (node (ref "CON19") (pin "70") (pinfunction "3V3_3_70") (pintype "passive"))
      (node (ref "CON19") (pin "72") (pinfunction "3V3_4_72") (pintype "passive"))
      (node (ref "CON19") (pin "74") (pinfunction "3V3_5_74") (pintype "passive"))
      (node (ref "L8") (pin "2") (pinfunction "2_2") (pintype "passive"))
      (node (ref "R290") (pin "1") (pinfunction "1_1") (pintype "passive"))
      (node (ref "R314") (pin "2") (pinfunction "2_2") (pintype "passive"))
      (node (ref "TP17") (pin "1") (pinfunction "1_1") (pintype "passive"))
    )
    (net (code "52") (name "VDD_3V3_SOM_OUT") (class "Default")
      (node (ref "R313") (pin "2") (pinfunction "2_2") (pintype "passive"))
    )
    (net (code "53") (name "VDD_12V_MAIN") (class "Default")
      (node (ref "C264") (pin "1") (pinfunction "1_1") (pintype "passive"))
      (node (ref "C265") (pin "1") (pinfunction "1_1") (pintype "passive"))
      (node (ref "C266") (pin "1") (pinfunction "1_1") (pintype "passive"))
      (node (ref "U49") (pin "5") (pinfunction "VIN_5") (pintype "power_in"))
    )
    (net (code "54") (name "VFFE_VIO_1V8") (class "Default")
      (node (ref "CON19") (pin "65") (pinfunction "ANTCTL3_65") (pintype "passive"))
    )
    (net (code "55") (name "XL9555_P02{slash}4G_nRST{slash}5G_RSTn{slash}3V3") (class "Default")
      (node (ref "Q13") (pin "1") (pinfunction "B_1") (pintype "passive"))
      (node (ref "R312") (pin "1") (pinfunction "1_1") (pintype "passive"))
    )
    (net (code "56") (name "XL9555_P14{slash}SDIO_EN{slash}KEYB_PWROFFn{slash}LVDS_DEN{slash}DEVSLP{slash}3V3") (class "Default")
      (node (ref "R285") (pin "1") (pinfunction "1_1") (pintype "passive"))
      (node (ref "R293") (pin "2") (pinfunction "2_2") (pintype "passive"))
    )
    (net (code "57") (name "unconnected-(CON19-ANTCTL0-Pad59)") (class "Default")
      (node (ref "CON19") (pin "59") (pinfunction "ANTCTL0_59") (pintype "passive+no_connect"))
    )
    (net (code "58") (name "unconnected-(CON19-ANTCTL1-Pad61)") (class "Default")
      (node (ref "CON19") (pin "61") (pinfunction "ANTCTL1_61") (pintype "passive+no_connect"))
    )
    (net (code "59") (name "unconnected-(CON19-ANTCTL2-Pad63)") (class "Default")
      (node (ref "CON19") (pin "63") (pinfunction "ANTCTL2_63") (pintype "passive+no_connect"))
    )
    (net (code "60") (name "unconnected-(CON19-COEX3-Pad60)") (class "Default")
      (node (ref "CON19") (pin "60") (pinfunction "COEX3_60") (pintype "passive+no_connect"))
    )
    (net (code "61") (name "unconnected-(CON19-COEX_RXD-Pad64)") (class "Default")
      (node (ref "CON19") (pin "64") (pinfunction "COEX_RXD_64") (pintype "passive+no_connect"))
    )
    (net (code "62") (name "unconnected-(CON19-COEX_TXD-Pad62)") (class "Default")
      (node (ref "CON19") (pin "62") (pinfunction "COEX_TXD_62") (pintype "passive+no_connect"))
    )
    (net (code "63") (name "unconnected-(CON19-DPR-Pad25)") (class "Default")
      (node (ref "CON19") (pin "25") (pinfunction "DPR_25") (pintype "passive+no_connect"))
    )
    (net (code "64") (name "unconnected-(CON19-GPIO_0{slash}SMB_CLK-Pad40)") (class "Default")
      (node (ref "CON19") (pin "40") (pinfunction "GPIO_0/SMB_CLK_40") (pintype "passive+no_connect"))
    )
    (net (code "65") (name "unconnected-(CON19-GPIO_1{slash}SMB_DATA-Pad42)") (class "Default")
      (node (ref "CON19") (pin "42") (pinfunction "GPIO_1/SMB_DATA_42") (pintype "passive+no_connect"))
    )
    (net (code "66") (name "unconnected-(CON19-GPIO_2{slash}ALERT#-Pad44)") (class "Default")
      (node (ref "CON19") (pin "44") (pinfunction "GPIO_2/ALERT#_44") (pintype "passive+no_connect"))
    )
    (net (code "67") (name "unconnected-(CON19-GPIO_3-Pad46)") (class "Default")
      (node (ref "CON19") (pin "46") (pinfunction "GPIO_3_46") (pintype "passive+no_connect"))
    )
    (net (code "68") (name "unconnected-(CON19-GPIO_4-Pad48)") (class "Default")
      (node (ref "CON19") (pin "48") (pinfunction "GPIO_4_48") (pintype "passive+no_connect"))
    )
    (net (code "69") (name "unconnected-(CON19-GPIO_5-Pad20)") (class "Default")
      (node (ref "CON19") (pin "20") (pinfunction "GPIO_5_20") (pintype "passive+no_connect"))
    )
    (net (code "70") (name "unconnected-(CON19-GPIO_6-Pad22)") (class "Default")
      (node (ref "CON19") (pin "22") (pinfunction "GPIO_6_22") (pintype "passive+no_connect"))
    )
    (net (code "71") (name "unconnected-(CON19-GPIO_7-Pad24)") (class "Default")
      (node (ref "CON19") (pin "24") (pinfunction "GPIO_7_24") (pintype "passive+no_connect"))
    )
    (net (code "72") (name "unconnected-(CON19-GPIO_8-Pad28)") (class "Default")
      (node (ref "CON19") (pin "28") (pinfunction "GPIO_8_28") (pintype "passive+no_connect"))
    )
    (net (code "73") (name "unconnected-(CON19-GPIO_10-Pad26)") (class "Default")
      (node (ref "CON19") (pin "26") (pinfunction "GPIO_10_26") (pintype "passive+no_connect"))
    )
    (net (code "74") (name "unconnected-(CON19-H1-Pad78)") (class "Default")
      (node (ref "CON19") (pin "78") (pinfunction "H1_78") (pintype "passive+no_connect"))
    )
    (net (code "75") (name "unconnected-(CON19-H2-Pad79)") (class "Default")
      (node (ref "CON19") (pin "79") (pinfunction "H2_79") (pintype "passive+no_connect"))
    )
    (net (code "76") (name "unconnected-(CON19-H3-Pad80)") (class "Default")
      (node (ref "CON19") (pin "80") (pinfunction "H3_80") (pintype "passive+no_connect"))
    )
    (net (code "77") (name "unconnected-(CON19-N{slash}C_1-Pad56)") (class "Default")
      (node (ref "CON19") (pin "56") (pinfunction "N/C_1_56") (pintype "passive+no_connect"))
    )
    (net (code "78") (name "unconnected-(CON19-N{slash}C_2-Pad58)") (class "Default")
      (node (ref "CON19") (pin "58") (pinfunction "N/C_2_58") (pintype "passive+no_connect"))
    )
    (net (code "79") (name "unconnected-(CON19-PAD1-Pad76)") (class "Default")
      (node (ref "CON19") (pin "76") (pinfunction "PAD1_76") (pintype "passive+no_connect"))
    )
    (net (code "80") (name "unconnected-(CON19-PAD2-Pad77)") (class "Default")
      (node (ref "CON19") (pin "77") (pinfunction "PAD2_77") (pintype "passive+no_connect"))
    )
    (net (code "81") (name "unconnected-(CON19-PERn1{slash}USB3.0-Rx-{slash}SSIC-RxN-Pad29)") (class "Default")
      (node (ref "CON19") (pin "29") (pinfunction "PERn1/USB3.0-Rx-/SSIC-RxN_29") (pintype "passive+no_connect"))
    )
    (net (code "82") (name "unconnected-(CON19-PERp1{slash}USB3.0-Rx+{slash}SSIC-RxP-Pad31)") (class "Default")
      (node (ref "CON19") (pin "31") (pinfunction "PERp1/USB3.0-Rx+/SSIC-RxP_31") (pintype "passive+no_connect"))
    )
    (net (code "83") (name "unconnected-(CON19-PETn1{slash}USB3.0-Tx-{slash}SSIC-TxN-Pad35)") (class "Default")
      (node (ref "CON19") (pin "35") (pinfunction "PETn1/USB3.0-Tx-/SSIC-TxN_35") (pintype "passive+no_connect"))
    )
    (net (code "84") (name "unconnected-(CON19-PETp1{slash}USB3.0-Tx+{slash}SSIC-TxP-Pad37)") (class "Default")
      (node (ref "CON19") (pin "37") (pinfunction "PETp1/USB3.0-Tx+/SSIC-TxP_37") (pintype "passive+no_connect"))
    )
    (net (code "85") (name "unconnected-(CON19-SIM_DETECT-Pad66)") (class "Default")
      (node (ref "CON19") (pin "66") (pinfunction "SIM_DETECT_66") (pintype "passive+no_connect"))
    )
    (net (code "86") (name "unconnected-(CON19-SUSCLK-Pad68)") (class "Default")
      (node (ref "CON19") (pin "68") (pinfunction "SUSCLK_68") (pintype "passive+no_connect"))
    )
    (net (code "87") (name "unconnected-(CON19-W_DISABLE1#-Pad8)") (class "Default")
      (node (ref "CON19") (pin "8") (pinfunction "W_DISABLE1#_8") (pintype "passive+no_connect"))
    )
    (net (code "88") (name "unconnected-(H7-Pad1)") (class "Default")
      (node (ref "H7") (pin "1") (pinfunction "1_1") (pintype "passive+no_connect"))
    )
    (net (code "89") (name "unconnected-(H8-Pad1)") (class "Default")
      (node (ref "H8") (pin "1") (pinfunction "1_1") (pintype "passive+no_connect"))
    )
    (net (code "90") (name "unconnected-(U48-Pad6)") (class "Default")
      (node (ref "U48") (pin "6") (pinfunction "6_6") (pintype "passive+no_connect"))
    )
  )
)
